# cnc_driver_5.net
KiCad netlist of a schematic drawn in EAGLE
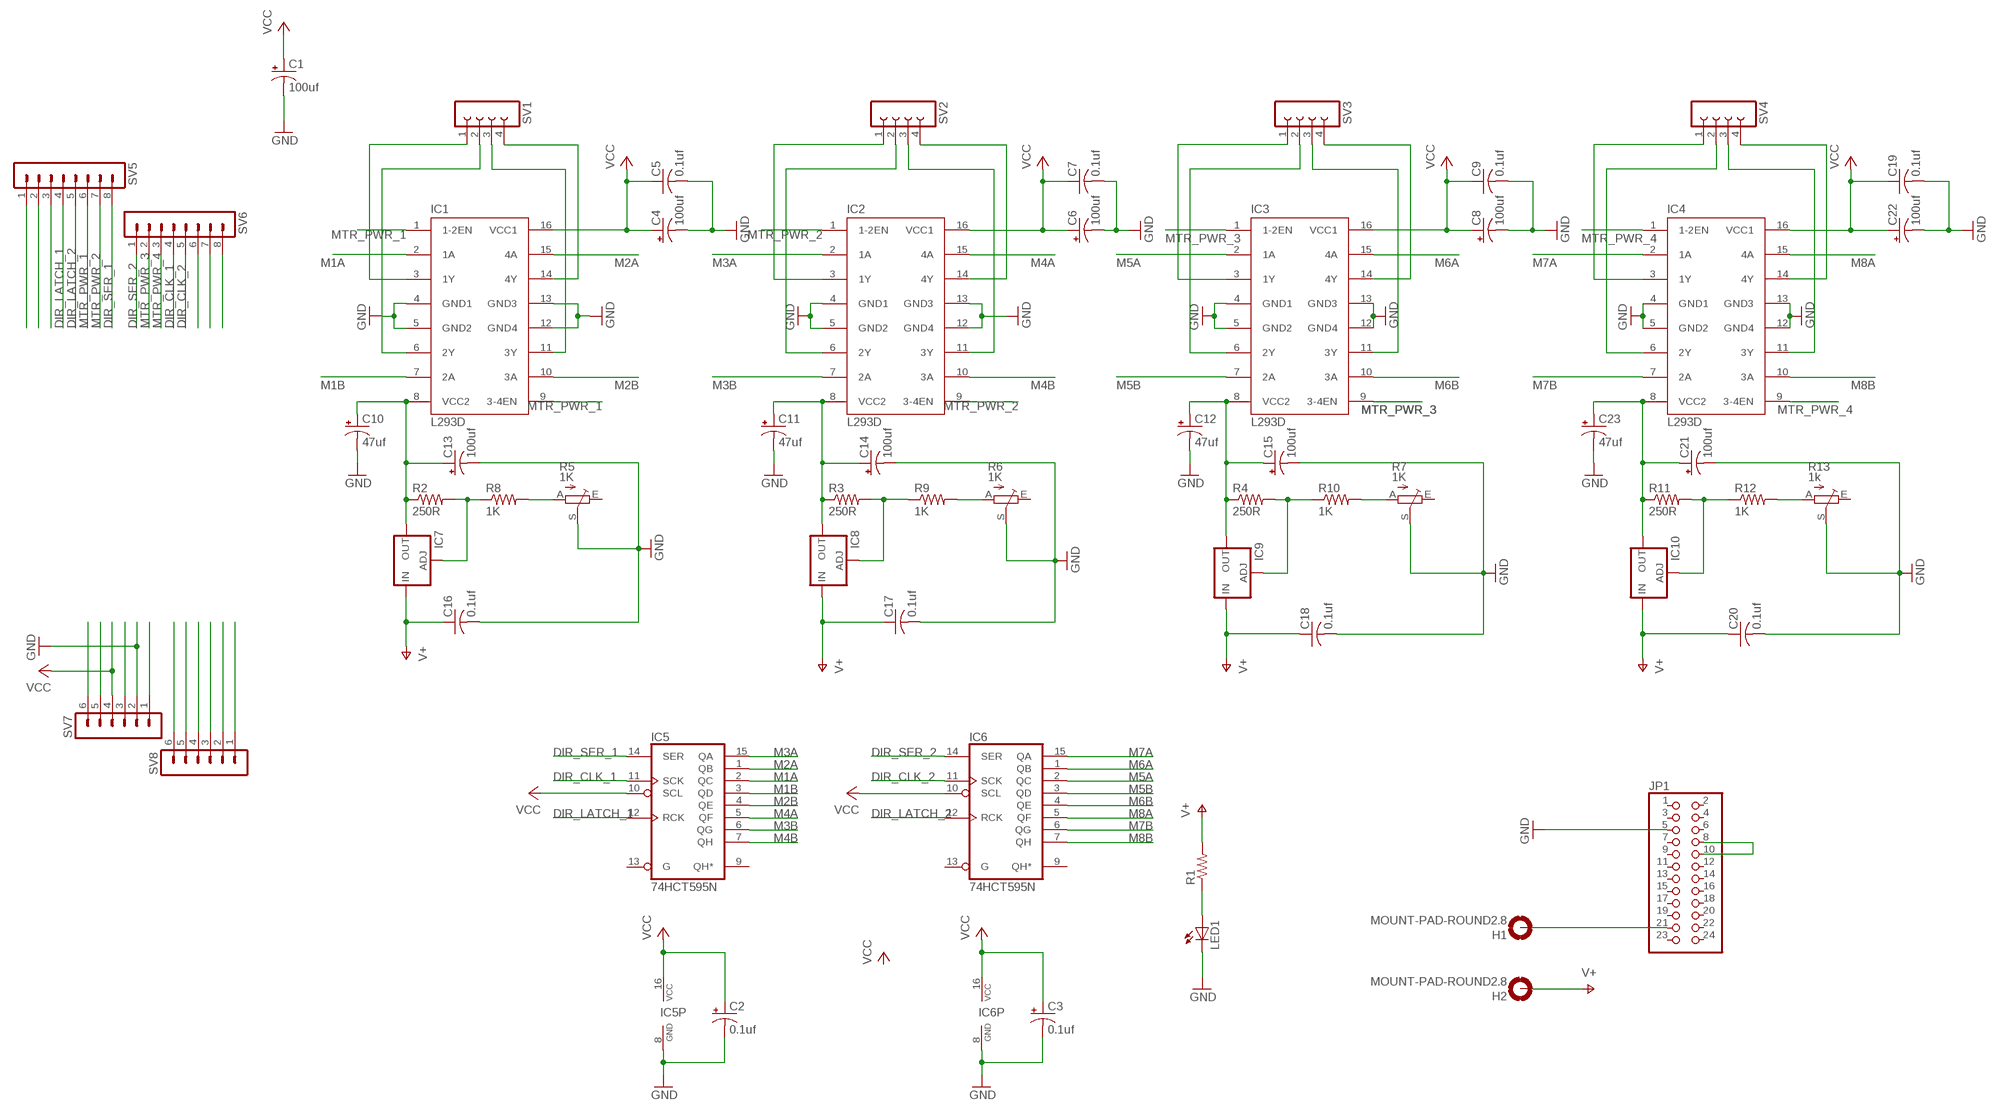
[diagram p0: schematic, sheet 1]

(export (version "E")
  (design (tool "Eeschema 10.0.6"))
  (components
    (comp (ref "C1")
      (value "100uf")
      (footprint "eagle-import:E2-5")
      (libsource (lib "eagle-import") (part "CPOL-USE2-5"))
    )
    (comp (ref "C2")
      (value "0.1uf")
      (footprint "eagle-import:E2-5")
      (libsource (lib "eagle-import") (part "CPOL-USE2-5"))
    )
    (comp (ref "C3")
      (value "0.1uf")
      (footprint "eagle-import:E2-5")
      (libsource (lib "eagle-import") (part "CPOL-USE2-5"))
    )
    (comp (ref "C4")
      (value "100uf")
      (footprint "eagle-import:E2-5")
      (libsource (lib "eagle-import") (part "CPOL-USE2-5"))
    )
    (comp (ref "C5")
      (value "0.1uf")
      (footprint "eagle-import:C025-025X050")
      (libsource (lib "eagle-import") (part "C-US025-025X050"))
    )
    (comp (ref "C6")
      (value "100uf")
      (footprint "eagle-import:E2-5")
      (libsource (lib "eagle-import") (part "CPOL-USE2-5"))
    )
    (comp (ref "C7")
      (value "0.1uf")
      (footprint "eagle-import:C025-025X050")
      (libsource (lib "eagle-import") (part "C-US025-025X050"))
    )
    (comp (ref "C8")
      (value "100uf")
      (footprint "eagle-import:E2-5")
      (libsource (lib "eagle-import") (part "CPOL-USE2-5"))
    )
    (comp (ref "C9")
      (value "0.1uf")
      (footprint "eagle-import:C025-025X050")
      (libsource (lib "eagle-import") (part "C-US025-025X050"))
    )
    (comp (ref "C10")
      (value "47uf")
      (footprint "eagle-import:E2-5")
      (libsource (lib "eagle-import") (part "CPOL-USE2-5"))
    )
    (comp (ref "C11")
      (value "47uf")
      (footprint "eagle-import:E2-5")
      (libsource (lib "eagle-import") (part "CPOL-USE2-5"))
    )
    (comp (ref "C12")
      (value "47uf")
      (footprint "eagle-import:E2-5")
      (libsource (lib "eagle-import") (part "CPOL-USE2-5"))
    )
    (comp (ref "C13")
      (value "100uf")
      (footprint "eagle-import:E3,5-8")
      (libsource (lib "eagle-import") (part "CPOL-USE3.5-8"))
    )
    (comp (ref "C14")
      (value "100uf")
      (footprint "eagle-import:E3,5-8")
      (libsource (lib "eagle-import") (part "CPOL-USE3.5-8"))
    )
    (comp (ref "C15")
      (value "100uf")
      (footprint "eagle-import:E3,5-8")
      (libsource (lib "eagle-import") (part "CPOL-USE3.5-8"))
    )
    (comp (ref "C16")
      (value "0.1uf")
      (footprint "eagle-import:C025-024X044")
      (libsource (lib "eagle-import") (part "C-US025-024X044"))
    )
    (comp (ref "C17")
      (value "0.1uf")
      (footprint "eagle-import:C025-024X044")
      (libsource (lib "eagle-import") (part "C-US025-024X044"))
    )
    (comp (ref "C18")
      (value "0.1uf")
      (footprint "eagle-import:C025-024X044")
      (libsource (lib "eagle-import") (part "C-US025-024X044"))
    )
    (comp (ref "C19")
      (value "0.1uf")
      (footprint "eagle-import:C025-025X050")
      (libsource (lib "eagle-import") (part "C-US025-025X050"))
    )
    (comp (ref "C20")
      (value "0.1uf")
      (footprint "eagle-import:C025-025X050")
      (libsource (lib "eagle-import") (part "C-US025-025X050"))
    )
    (comp (ref "C21")
      (value "100uf")
      (footprint "eagle-import:E3,5-8")
      (libsource (lib "eagle-import") (part "CPOL-USE3.5-8"))
    )
    (comp (ref "C22")
      (value "100uf")
      (footprint "eagle-import:E3,5-8")
      (libsource (lib "eagle-import") (part "CPOL-USE3.5-8"))
    )
    (comp (ref "C23")
      (value "47uf")
      (footprint "eagle-import:E3,5-8")
      (libsource (lib "eagle-import") (part "CPOL-USE3.5-8"))
    )
    (comp (ref "H1")
      (value "MOUNT-PAD-ROUND2.8")
      (footprint "eagle-import:2,8-PAD")
      (libsource (lib "eagle-import") (part "MOUNT-PAD-ROUND2.8"))
    )
    (comp (ref "H2")
      (value "MOUNT-PAD-ROUND2.8")
      (footprint "eagle-import:2,8-PAD")
      (libsource (lib "eagle-import") (part "MOUNT-PAD-ROUND2.8"))
    )
    (comp (ref "IC1")
      (value "L293D")
      (footprint "eagle-import:DIL16")
      (libsource (lib "eagle-import") (part "L293D"))
    )
    (comp (ref "IC2")
      (value "L293D")
      (footprint "eagle-import:DIL16")
      (libsource (lib "eagle-import") (part "L293D"))
    )
    (comp (ref "IC3")
      (value "L293D")
      (footprint "eagle-import:DIL16")
      (libsource (lib "eagle-import") (part "L293D"))
    )
    (comp (ref "IC4")
      (value "L293D")
      (footprint "eagle-import:DIL16")
      (libsource (lib "eagle-import") (part "L293D"))
    )
    (comp (ref "IC5")
      (value "74HCT595N")
      (footprint "eagle-import:DIL16")
      (libsource (lib "eagle-import") (part "74595NHCT"))
    )
    (comp (ref "IC6")
      (value "74HCT595N")
      (footprint "eagle-import:DIL16")
      (libsource (lib "eagle-import") (part "74595NHCT"))
    )
    (comp (ref "IC7")
      (value "LM317TS")
      (footprint "eagle-import:317TS")
      (libsource (lib "eagle-import") (part "LM317TS"))
    )
    (comp (ref "IC8")
      (value "LM317TS")
      (footprint "eagle-import:317TS")
      (libsource (lib "eagle-import") (part "LM317TS"))
    )
    (comp (ref "IC9")
      (value "LM317TS")
      (footprint "eagle-import:317TS")
      (libsource (lib "eagle-import") (part "LM317TS"))
    )
    (comp (ref "IC10")
      (value "LM317TS")
      (footprint "eagle-import:317TS")
      (libsource (lib "eagle-import") (part "LM317TS"))
    )
    (comp (ref "JP1")
      (value "PINHD-2X12")
      (footprint "eagle-import:2X12")
      (libsource (lib "eagle-import") (part "PINHD-2X12"))
    )
    (comp (ref "LED1")
      (value "LED5MM")
      (footprint "eagle-import:LED5MM")
      (libsource (lib "eagle-import") (part "LED5MM"))
    )
    (comp (ref "R1")
      (value "R-US_0204/7")
      (footprint "eagle-import:0204_7")
      (libsource (lib "eagle-import") (part "R-US_0204/7"))
    )
    (comp (ref "R2")
      (value "250R")
      (footprint "eagle-import:0207_7")
      (libsource (lib "eagle-import") (part "R-US_0207/7"))
    )
    (comp (ref "R3")
      (value "250R")
      (footprint "eagle-import:0207_7")
      (libsource (lib "eagle-import") (part "R-US_0207/7"))
    )
    (comp (ref "R4")
      (value "250R")
      (footprint "eagle-import:0207_7")
      (libsource (lib "eagle-import") (part "R-US_0207/7"))
    )
    (comp (ref "R5")
      (value "1K")
      (footprint "eagle-import:CA9H")
      (libsource (lib "eagle-import") (part "TRIM_EU-CA9H"))
    )
    (comp (ref "R6")
      (value "1K")
      (footprint "eagle-import:CA9H")
      (libsource (lib "eagle-import") (part "TRIM_EU-CA9H"))
    )
    (comp (ref "R7")
      (value "1K")
      (footprint "eagle-import:CA9H")
      (libsource (lib "eagle-import") (part "TRIM_EU-CA9H"))
    )
    (comp (ref "R8")
      (value "1K")
      (footprint "eagle-import:0207_7")
      (libsource (lib "eagle-import") (part "R-US_0207/7"))
    )
    (comp (ref "R9")
      (value "1K")
      (footprint "eagle-import:0207_7")
      (libsource (lib "eagle-import") (part "R-US_0207/7"))
    )
    (comp (ref "R10")
      (value "1K")
      (footprint "eagle-import:0207_7")
      (libsource (lib "eagle-import") (part "R-US_0207/7"))
    )
    (comp (ref "R11")
      (value "250R")
      (footprint "eagle-import:0207_7")
      (libsource (lib "eagle-import") (part "R-US_0207/7"))
    )
    (comp (ref "R12")
      (value "1K")
      (footprint "eagle-import:0207_7")
      (libsource (lib "eagle-import") (part "R-US_0207/7"))
    )
    (comp (ref "R13")
      (value "1k")
      (footprint "eagle-import:CA9H")
      (libsource (lib "eagle-import") (part "TRIM_EU-CA9H"))
    )
    (comp (ref "SV1")
      (value "FE04-1")
      (footprint "eagle-import:FE04-1")
      (libsource (lib "eagle-import") (part "FE04-1"))
    )
    (comp (ref "SV2")
      (value "FE04-1")
      (footprint "eagle-import:FE04-1")
      (libsource (lib "eagle-import") (part "FE04-1"))
    )
    (comp (ref "SV3")
      (value "FE04-1")
      (footprint "eagle-import:FE04-1")
      (libsource (lib "eagle-import") (part "FE04-1"))
    )
    (comp (ref "SV4")
      (value "FE04-1")
      (footprint "eagle-import:FE04-1")
      (libsource (lib "eagle-import") (part "FE04-1"))
    )
    (comp (ref "SV5")
      (value "MA08-1")
      (footprint "eagle-import:MA08-1")
      (libsource (lib "eagle-import") (part "MA08-1"))
    )
    (comp (ref "SV6")
      (value "MA08-1")
      (footprint "eagle-import:MA08-1")
      (libsource (lib "eagle-import") (part "MA08-1"))
    )
    (comp (ref "SV7")
      (value "MA06-1")
      (footprint "eagle-import:MA06-1")
      (libsource (lib "eagle-import") (part "MA06-1"))
    )
    (comp (ref "SV8")
      (value "MA06-1")
      (footprint "eagle-import:MA06-1")
      (libsource (lib "eagle-import") (part "MA06-1"))
    )
  )
  (nets
    (net (code "1") (name "/DIR_CLK_1") (class "Default")
      (node (ref "IC5") (pin "11") (pinfunction "SCK_11") (pintype "input"))
      (node (ref "SV6") (pin "4") (pinfunction "4_4") (pintype "passive"))
    )
    (net (code "2") (name "/DIR_CLK_2") (class "Default")
      (node (ref "IC6") (pin "11") (pinfunction "SCK_11") (pintype "input"))
      (node (ref "SV6") (pin "5") (pinfunction "5_5") (pintype "passive"))
    )
    (net (code "3") (name "/DIR_LATCH_1") (class "Default")
      (node (ref "IC5") (pin "12") (pinfunction "RCK_12") (pintype "input"))
      (node (ref "SV5") (pin "4") (pinfunction "4_4") (pintype "passive"))
    )
    (net (code "4") (name "/DIR_LATCH_2") (class "Default")
      (node (ref "IC6") (pin "12") (pinfunction "RCK_12") (pintype "input"))
      (node (ref "SV5") (pin "5") (pinfunction "5_5") (pintype "passive"))
    )
    (net (code "5") (name "/DIR_SER_1") (class "Default")
      (node (ref "IC5") (pin "14") (pinfunction "SER_14") (pintype "input"))
      (node (ref "SV5") (pin "8") (pinfunction "8_8") (pintype "passive"))
    )
    (net (code "6") (name "/DIR_SER_2") (class "Default")
      (node (ref "IC6") (pin "14") (pinfunction "SER_14") (pintype "input"))
      (node (ref "SV6") (pin "1") (pinfunction "1_1") (pintype "passive"))
    )
    (net (code "7") (name "/M1A") (class "Default")
      (node (ref "IC1") (pin "2") (pinfunction "1A_2") (pintype "input"))
      (node (ref "IC5") (pin "2") (pinfunction "QC_2") (pintype "tri_state"))
    )
    (net (code "8") (name "/M1B") (class "Default")
      (node (ref "IC1") (pin "7") (pinfunction "2A_7") (pintype "input"))
      (node (ref "IC5") (pin "3") (pinfunction "QD_3") (pintype "tri_state"))
    )
    (net (code "9") (name "/M2A") (class "Default")
      (node (ref "IC1") (pin "15") (pinfunction "4A_15") (pintype "input"))
      (node (ref "IC5") (pin "1") (pinfunction "QB_1") (pintype "tri_state"))
    )
    (net (code "10") (name "/M2B") (class "Default")
      (node (ref "IC1") (pin "10") (pinfunction "3A_10") (pintype "input"))
      (node (ref "IC5") (pin "4") (pinfunction "QE_4") (pintype "tri_state"))
    )
    (net (code "11") (name "/M3A") (class "Default")
      (node (ref "IC2") (pin "2") (pinfunction "1A_2") (pintype "input"))
      (node (ref "IC5") (pin "15") (pinfunction "QA_15") (pintype "tri_state"))
    )
    (net (code "12") (name "/M3B") (class "Default")
      (node (ref "IC2") (pin "7") (pinfunction "2A_7") (pintype "input"))
      (node (ref "IC5") (pin "6") (pinfunction "QG_6") (pintype "tri_state"))
    )
    (net (code "13") (name "/M4A") (class "Default")
      (node (ref "IC2") (pin "15") (pinfunction "4A_15") (pintype "input"))
      (node (ref "IC5") (pin "5") (pinfunction "QF_5") (pintype "tri_state"))
    )
    (net (code "14") (name "/M4B") (class "Default")
      (node (ref "IC2") (pin "10") (pinfunction "3A_10") (pintype "input"))
      (node (ref "IC5") (pin "7") (pinfunction "QH_7") (pintype "tri_state"))
    )
    (net (code "15") (name "/M5A") (class "Default")
      (node (ref "IC3") (pin "2") (pinfunction "1A_2") (pintype "input"))
      (node (ref "IC6") (pin "2") (pinfunction "QC_2") (pintype "tri_state"))
    )
    (net (code "16") (name "/M5B") (class "Default")
      (node (ref "IC3") (pin "7") (pinfunction "2A_7") (pintype "input"))
      (node (ref "IC6") (pin "3") (pinfunction "QD_3") (pintype "tri_state"))
    )
    (net (code "17") (name "/M6A") (class "Default")
      (node (ref "IC3") (pin "15") (pinfunction "4A_15") (pintype "input"))
      (node (ref "IC6") (pin "1") (pinfunction "QB_1") (pintype "tri_state"))
    )
    (net (code "18") (name "/M6B") (class "Default")
      (node (ref "IC3") (pin "10") (pinfunction "3A_10") (pintype "input"))
      (node (ref "IC6") (pin "4") (pinfunction "QE_4") (pintype "tri_state"))
    )
    (net (code "19") (name "/M7A") (class "Default")
      (node (ref "IC4") (pin "2") (pinfunction "1A_2") (pintype "input"))
      (node (ref "IC6") (pin "15") (pinfunction "QA_15") (pintype "tri_state"))
    )
    (net (code "20") (name "/M7B") (class "Default")
      (node (ref "IC4") (pin "7") (pinfunction "2A_7") (pintype "input"))
      (node (ref "IC6") (pin "6") (pinfunction "QG_6") (pintype "tri_state"))
    )
    (net (code "21") (name "/M8A") (class "Default")
      (node (ref "IC4") (pin "15") (pinfunction "4A_15") (pintype "input"))
      (node (ref "IC6") (pin "5") (pinfunction "QF_5") (pintype "tri_state"))
    )
    (net (code "22") (name "/M8B") (class "Default")
      (node (ref "IC4") (pin "10") (pinfunction "3A_10") (pintype "input"))
      (node (ref "IC6") (pin "7") (pinfunction "QH_7") (pintype "tri_state"))
    )
    (net (code "23") (name "/MTR_PWR_1") (class "Default")
      (node (ref "IC1") (pin "1") (pinfunction "1-2EN_1") (pintype "input"))
      (node (ref "IC1") (pin "9") (pinfunction "3-4EN_9") (pintype "input"))
      (node (ref "SV5") (pin "6") (pinfunction "6_6") (pintype "passive"))
    )
    (net (code "24") (name "/MTR_PWR_2") (class "Default")
      (node (ref "IC2") (pin "1") (pinfunction "1-2EN_1") (pintype "input"))
      (node (ref "IC2") (pin "9") (pinfunction "3-4EN_9") (pintype "input"))
      (node (ref "SV5") (pin "7") (pinfunction "7_7") (pintype "passive"))
    )
    (net (code "25") (name "/MTR_PWR_3") (class "Default")
      (node (ref "IC3") (pin "1") (pinfunction "1-2EN_1") (pintype "input"))
      (node (ref "IC3") (pin "9") (pinfunction "3-4EN_9") (pintype "input"))
      (node (ref "SV6") (pin "2") (pinfunction "2_2") (pintype "passive"))
    )
    (net (code "26") (name "/MTR_PWR_4") (class "Default")
      (node (ref "IC4") (pin "1") (pinfunction "1-2EN_1") (pintype "input"))
      (node (ref "IC4") (pin "9") (pinfunction "3-4EN_9") (pintype "input"))
      (node (ref "SV6") (pin "3") (pinfunction "3_3") (pintype "passive"))
    )
    (net (code "27") (name "GND") (class "Default")
      (node (ref "C1") (pin "-") (pinfunction "-_-") (pintype "passive"))
      (node (ref "C10") (pin "-") (pinfunction "-_-") (pintype "passive"))
      (node (ref "C11") (pin "-") (pinfunction "-_-") (pintype "passive"))
      (node (ref "C12") (pin "-") (pinfunction "-_-") (pintype "passive"))
      (node (ref "C13") (pin "-") (pinfunction "-_-") (pintype "passive"))
      (node (ref "C14") (pin "-") (pinfunction "-_-") (pintype "passive"))
      (node (ref "C15") (pin "-") (pinfunction "-_-") (pintype "passive"))
      (node (ref "C16") (pin "2") (pinfunction "2_2") (pintype "passive"))
      (node (ref "C17") (pin "2") (pinfunction "2_2") (pintype "passive"))
      (node (ref "C18") (pin "2") (pinfunction "2_2") (pintype "passive"))
      (node (ref "C19") (pin "2") (pinfunction "2_2") (pintype "passive"))
      (node (ref "C2") (pin "-") (pinfunction "-_-") (pintype "passive"))
      (node (ref "C20") (pin "2") (pinfunction "2_2") (pintype "passive"))
      (node (ref "C21") (pin "-") (pinfunction "-_-") (pintype "passive"))
      (node (ref "C22") (pin "-") (pinfunction "-_-") (pintype "passive"))
      (node (ref "C23") (pin "-") (pinfunction "-_-") (pintype "passive"))
      (node (ref "C3") (pin "-") (pinfunction "-_-") (pintype "passive"))
      (node (ref "C4") (pin "-") (pinfunction "-_-") (pintype "passive"))
      (node (ref "C5") (pin "2") (pinfunction "2_2") (pintype "passive"))
      (node (ref "C6") (pin "-") (pinfunction "-_-") (pintype "passive"))
      (node (ref "C7") (pin "2") (pinfunction "2_2") (pintype "passive"))
      (node (ref "C8") (pin "-") (pinfunction "-_-") (pintype "passive"))
      (node (ref "C9") (pin "2") (pinfunction "2_2") (pintype "passive"))
      (node (ref "IC1") (pin "12") (pinfunction "GND4_12") (pintype "power_in"))
      (node (ref "IC1") (pin "13") (pinfunction "GND3_13") (pintype "power_in"))
      (node (ref "IC1") (pin "4") (pinfunction "GND1_4") (pintype "power_in"))
      (node (ref "IC1") (pin "5") (pinfunction "GND2_5") (pintype "power_in"))
      (node (ref "IC2") (pin "12") (pinfunction "GND4_12") (pintype "power_in"))
      (node (ref "IC2") (pin "13") (pinfunction "GND3_13") (pintype "power_in"))
      (node (ref "IC2") (pin "4") (pinfunction "GND1_4") (pintype "power_in"))
      (node (ref "IC2") (pin "5") (pinfunction "GND2_5") (pintype "power_in"))
      (node (ref "IC3") (pin "12") (pinfunction "GND4_12") (pintype "power_in"))
      (node (ref "IC3") (pin "13") (pinfunction "GND3_13") (pintype "power_in"))
      (node (ref "IC3") (pin "4") (pinfunction "GND1_4") (pintype "power_in"))
      (node (ref "IC3") (pin "5") (pinfunction "GND2_5") (pintype "power_in"))
      (node (ref "IC4") (pin "12") (pinfunction "GND4_12") (pintype "power_in"))
      (node (ref "IC4") (pin "13") (pinfunction "GND3_13") (pintype "power_in"))
      (node (ref "IC4") (pin "4") (pinfunction "GND1_4") (pintype "power_in"))
      (node (ref "IC4") (pin "5") (pinfunction "GND2_5") (pintype "power_in"))
      (node (ref "IC5") (pin "8") (pinfunction "GND_8") (pintype "power_in"))
      (node (ref "IC6") (pin "8") (pinfunction "GND_8") (pintype "power_in"))
      (node (ref "JP1") (pin "5") (pinfunction "5_5") (pintype "passive"))
      (node (ref "LED1") (pin "K") (pinfunction "C_K") (pintype "passive"))
      (node (ref "R13") (pin "S") (pinfunction "S_S") (pintype "passive"))
      (node (ref "R5") (pin "S") (pinfunction "S_S") (pintype "passive"))
      (node (ref "R6") (pin "S") (pinfunction "S_S") (pintype "passive"))
      (node (ref "R7") (pin "S") (pinfunction "S_S") (pintype "passive"))
      (node (ref "SV7") (pin "2") (pinfunction "2_2") (pintype "passive"))
    )
    (net (code "28") (name "Net-(H1-MOUNT)") (class "Default")
      (node (ref "H1") (pin "B2,8") (pinfunction "MOUNT_B2,8") (pintype "passive"))
      (node (ref "JP1") (pin "21") (pinfunction "21_21") (pintype "passive"))
    )
    (net (code "29") (name "Net-(IC1-1Y)") (class "Default")
      (node (ref "IC1") (pin "3") (pinfunction "1Y_3") (pintype "output"))
      (node (ref "SV1") (pin "1") (pinfunction "1_1") (pintype "passive"))
    )
    (net (code "30") (name "Net-(IC1-2Y)") (class "Default")
      (node (ref "IC1") (pin "6") (pinfunction "2Y_6") (pintype "output"))
      (node (ref "SV1") (pin "2") (pinfunction "2_2") (pintype "passive"))
    )
    (net (code "31") (name "Net-(IC1-3Y)") (class "Default")
      (node (ref "IC1") (pin "11") (pinfunction "3Y_11") (pintype "output"))
      (node (ref "SV1") (pin "3") (pinfunction "3_3") (pintype "passive"))
    )
    (net (code "32") (name "Net-(IC1-4Y)") (class "Default")
      (node (ref "IC1") (pin "14") (pinfunction "4Y_14") (pintype "output"))
      (node (ref "SV1") (pin "4") (pinfunction "4_4") (pintype "passive"))
    )
    (net (code "33") (name "Net-(IC1-VCC2)") (class "Default")
      (node (ref "C10") (pin "+") (pinfunction "+_+") (pintype "passive"))
      (node (ref "C13") (pin "+") (pinfunction "+_+") (pintype "passive"))
      (node (ref "IC1") (pin "8") (pinfunction "VCC2_8") (pintype "power_in"))
      (node (ref "IC7") (pin "2") (pinfunction "OUT_2") (pintype "passive"))
      (node (ref "R2") (pin "1") (pinfunction "1_1") (pintype "passive"))
    )
    (net (code "34") (name "Net-(IC2-1Y)") (class "Default")
      (node (ref "IC2") (pin "3") (pinfunction "1Y_3") (pintype "output"))
      (node (ref "SV2") (pin "1") (pinfunction "1_1") (pintype "passive"))
    )
    (net (code "35") (name "Net-(IC2-2Y)") (class "Default")
      (node (ref "IC2") (pin "6") (pinfunction "2Y_6") (pintype "output"))
      (node (ref "SV2") (pin "2") (pinfunction "2_2") (pintype "passive"))
    )
    (net (code "36") (name "Net-(IC2-3Y)") (class "Default")
      (node (ref "IC2") (pin "11") (pinfunction "3Y_11") (pintype "output"))
      (node (ref "SV2") (pin "3") (pinfunction "3_3") (pintype "passive"))
    )
    (net (code "37") (name "Net-(IC2-4Y)") (class "Default")
      (node (ref "IC2") (pin "14") (pinfunction "4Y_14") (pintype "output"))
      (node (ref "SV2") (pin "4") (pinfunction "4_4") (pintype "passive"))
    )
    (net (code "38") (name "Net-(IC2-VCC2)") (class "Default")
      (node (ref "C11") (pin "+") (pinfunction "+_+") (pintype "passive"))
      (node (ref "C14") (pin "+") (pinfunction "+_+") (pintype "passive"))
      (node (ref "IC2") (pin "8") (pinfunction "VCC2_8") (pintype "power_in"))
      (node (ref "IC8") (pin "2") (pinfunction "OUT_2") (pintype "passive"))
      (node (ref "R3") (pin "1") (pinfunction "1_1") (pintype "passive"))
    )
    (net (code "39") (name "Net-(IC3-1Y)") (class "Default")
      (node (ref "IC3") (pin "3") (pinfunction "1Y_3") (pintype "output"))
      (node (ref "SV3") (pin "1") (pinfunction "1_1") (pintype "passive"))
    )
    (net (code "40") (name "Net-(IC3-2Y)") (class "Default")
      (node (ref "IC3") (pin "6") (pinfunction "2Y_6") (pintype "output"))
      (node (ref "SV3") (pin "2") (pinfunction "2_2") (pintype "passive"))
    )
    (net (code "41") (name "Net-(IC3-3Y)") (class "Default")
      (node (ref "IC3") (pin "11") (pinfunction "3Y_11") (pintype "output"))
      (node (ref "SV3") (pin "3") (pinfunction "3_3") (pintype "passive"))
    )
    (net (code "42") (name "Net-(IC3-4Y)") (class "Default")
      (node (ref "IC3") (pin "14") (pinfunction "4Y_14") (pintype "output"))
      (node (ref "SV3") (pin "4") (pinfunction "4_4") (pintype "passive"))
    )
    (net (code "43") (name "Net-(IC3-VCC2)") (class "Default")
      (node (ref "C12") (pin "+") (pinfunction "+_+") (pintype "passive"))
      (node (ref "C15") (pin "+") (pinfunction "+_+") (pintype "passive"))
      (node (ref "IC3") (pin "8") (pinfunction "VCC2_8") (pintype "power_in"))
      (node (ref "IC9") (pin "2") (pinfunction "OUT_2") (pintype "passive"))
      (node (ref "R4") (pin "1") (pinfunction "1_1") (pintype "passive"))
    )
    (net (code "44") (name "Net-(IC4-1Y)") (class "Default")
      (node (ref "IC4") (pin "3") (pinfunction "1Y_3") (pintype "output"))
      (node (ref "SV4") (pin "1") (pinfunction "1_1") (pintype "passive"))
    )
    (net (code "45") (name "Net-(IC4-2Y)") (class "Default")
      (node (ref "IC4") (pin "6") (pinfunction "2Y_6") (pintype "output"))
      (node (ref "SV4") (pin "2") (pinfunction "2_2") (pintype "passive"))
    )
    (net (code "46") (name "Net-(IC4-3Y)") (class "Default")
      (node (ref "IC4") (pin "11") (pinfunction "3Y_11") (pintype "output"))
      (node (ref "SV4") (pin "3") (pinfunction "3_3") (pintype "passive"))
    )
    (net (code "47") (name "Net-(IC4-4Y)") (class "Default")
      (node (ref "IC4") (pin "14") (pinfunction "4Y_14") (pintype "output"))
      (node (ref "SV4") (pin "4") (pinfunction "4_4") (pintype "passive"))
    )
    (net (code "48") (name "Net-(IC7-ADJ)") (class "Default")
      (node (ref "IC7") (pin "1") (pinfunction "ADJ_1") (pintype "input"))
      (node (ref "R2") (pin "2") (pinfunction "2_2") (pintype "passive"))
      (node (ref "R8") (pin "1") (pinfunction "1_1") (pintype "passive"))
    )
    (net (code "49") (name "Net-(IC8-ADJ)") (class "Default")
      (node (ref "IC8") (pin "1") (pinfunction "ADJ_1") (pintype "input"))
      (node (ref "R3") (pin "2") (pinfunction "2_2") (pintype "passive"))
      (node (ref "R9") (pin "1") (pinfunction "1_1") (pintype "passive"))
    )
    (net (code "50") (name "Net-(IC9-ADJ)") (class "Default")
      (node (ref "IC9") (pin "1") (pinfunction "ADJ_1") (pintype "input"))
      (node (ref "R10") (pin "1") (pinfunction "1_1") (pintype "passive"))
      (node (ref "R4") (pin "2") (pinfunction "2_2") (pintype "passive"))
    )
    (net (code "51") (name "Net-(IC10-ADJ)") (class "Default")
      (node (ref "IC10") (pin "1") (pinfunction "ADJ_1") (pintype "input"))
      (node (ref "R11") (pin "2") (pinfunction "2_2") (pintype "passive"))
      (node (ref "R12") (pin "1") (pinfunction "1_1") (pintype "passive"))
    )
    (net (code "52") (name "Net-(IC10-OUT)") (class "Default")
      (node (ref "C21") (pin "+") (pinfunction "+_+") (pintype "passive"))
      (node (ref "C23") (pin "+") (pinfunction "+_+") (pintype "passive"))
      (node (ref "IC10") (pin "2") (pinfunction "OUT_2") (pintype "passive"))
      (node (ref "IC4") (pin "8") (pinfunction "VCC2_8") (pintype "power_in"))
      (node (ref "R11") (pin "1") (pinfunction "1_1") (pintype "passive"))
    )
    (net (code "53") (name "Net-(JP1-Pad10)") (class "Default")
      (node (ref "JP1") (pin "10") (pinfunction "10_10") (pintype "passive"))
      (node (ref "JP1") (pin "8") (pinfunction "8_8") (pintype "passive"))
    )
    (net (code "54") (name "Net-(LED1-PadA)") (class "Default")
      (node (ref "LED1") (pin "A") (pinfunction "A_A") (pintype "passive"))
      (node (ref "R1") (pin "1") (pinfunction "1_1") (pintype "passive"))
    )
    (net (code "55") (name "Net-(R5-PadA)") (class "Default")
      (node (ref "R5") (pin "A") (pinfunction "A_A") (pintype "passive"))
      (node (ref "R8") (pin "2") (pinfunction "2_2") (pintype "passive"))
    )
    (net (code "56") (name "Net-(R6-PadA)") (class "Default")
      (node (ref "R6") (pin "A") (pinfunction "A_A") (pintype "passive"))
      (node (ref "R9") (pin "2") (pinfunction "2_2") (pintype "passive"))
    )
    (net (code "57") (name "Net-(R10-Pad2)") (class "Default")
      (node (ref "R10") (pin "2") (pinfunction "2_2") (pintype "passive"))
      (node (ref "R7") (pin "A") (pinfunction "A_A") (pintype "passive"))
    )
    (net (code "58") (name "Net-(R12-Pad2)") (class "Default")
      (node (ref "R12") (pin "2") (pinfunction "2_2") (pintype "passive"))
      (node (ref "R13") (pin "A") (pinfunction "A_A") (pintype "passive"))
    )
    (net (code "59") (name "V+") (class "Default")
      (node (ref "C16") (pin "1") (pinfunction "1_1") (pintype "passive"))
      (node (ref "C17") (pin "1") (pinfunction "1_1") (pintype "passive"))
      (node (ref "C18") (pin "1") (pinfunction "1_1") (pintype "passive"))
      (node (ref "C20") (pin "1") (pinfunction "1_1") (pintype "passive"))
      (node (ref "H2") (pin "B2,8") (pinfunction "MOUNT_B2,8") (pintype "passive"))
      (node (ref "IC10") (pin "3") (pinfunction "IN_3") (pintype "input"))
      (node (ref "IC7") (pin "3") (pinfunction "IN_3") (pintype "input"))
      (node (ref "IC8") (pin "3") (pinfunction "IN_3") (pintype "input"))
      (node (ref "IC9") (pin "3") (pinfunction "IN_3") (pintype "input"))
      (node (ref "R1") (pin "2") (pinfunction "2_2") (pintype "passive"))
    )
    (net (code "60") (name "VCC") (class "Default")
      (node (ref "C1") (pin "+") (pinfunction "+_+") (pintype "passive"))
      (node (ref "C19") (pin "1") (pinfunction "1_1") (pintype "passive"))
      (node (ref "C2") (pin "+") (pinfunction "+_+") (pintype "passive"))
      (node (ref "C22") (pin "+") (pinfunction "+_+") (pintype "passive"))
      (node (ref "C3") (pin "+") (pinfunction "+_+") (pintype "passive"))
      (node (ref "C4") (pin "+") (pinfunction "+_+") (pintype "passive"))
      (node (ref "C5") (pin "1") (pinfunction "1_1") (pintype "passive"))
      (node (ref "C6") (pin "+") (pinfunction "+_+") (pintype "passive"))
      (node (ref "C7") (pin "1") (pinfunction "1_1") (pintype "passive"))
      (node (ref "C8") (pin "+") (pinfunction "+_+") (pintype "passive"))
      (node (ref "C9") (pin "1") (pinfunction "1_1") (pintype "passive"))
      (node (ref "IC1") (pin "16") (pinfunction "VCC1_16") (pintype "power_in"))
      (node (ref "IC2") (pin "16") (pinfunction "VCC1_16") (pintype "power_in"))
      (node (ref "IC3") (pin "16") (pinfunction "VCC1_16") (pintype "power_in"))
      (node (ref "IC4") (pin "16") (pinfunction "VCC1_16") (pintype "power_in"))
      (node (ref "IC5") (pin "10") (pinfunction "SCL_10") (pintype "input"))
      (node (ref "IC5") (pin "16") (pinfunction "VCC_16") (pintype "power_in"))
      (node (ref "IC6") (pin "10") (pinfunction "SCL_10") (pintype "input"))
      (node (ref "IC6") (pin "16") (pinfunction "VCC_16") (pintype "power_in"))
      (node (ref "SV7") (pin "4") (pinfunction "4_4") (pintype "passive"))
    )
    (net (code "61") (name "unconnected-(IC5A-G-Pad13)") (class "Default")
      (node (ref "IC5") (pin "13") (pinfunction "G_13") (pintype "input"))
    )
    (net (code "62") (name "unconnected-(IC5A-QH*-Pad9)") (class "Default")
      (node (ref "IC5") (pin "9") (pinfunction "QH*_9") (pintype "tri_state"))
    )
    (net (code "63") (name "unconnected-(IC6A-G-Pad13)") (class "Default")
      (node (ref "IC6") (pin "13") (pinfunction "G_13") (pintype "input"))
    )
    (net (code "64") (name "unconnected-(IC6A-QH*-Pad9)") (class "Default")
      (node (ref "IC6") (pin "9") (pinfunction "QH*_9") (pintype "tri_state"))
    )
    (net (code "65") (name "unconnected-(JP1-Pad1)") (class "Default")
      (node (ref "JP1") (pin "1") (pinfunction "1_1") (pintype "passive"))
    )
    (net (code "66") (name "unconnected-(JP1-Pad2)") (class "Default")
      (node (ref "JP1") (pin "2") (pinfunction "2_2") (pintype "passive"))
    )
    (net (code "67") (name "unconnected-(JP1-Pad3)") (class "Default")
      (node (ref "JP1") (pin "3") (pinfunction "3_3") (pintype "passive"))
    )
    (net (code "68") (name "unconnected-(JP1-Pad4)") (class "Default")
      (node (ref "JP1") (pin "4") (pinfunction "4_4") (pintype "passive"))
    )
    (net (code "69") (name "unconnected-(JP1-Pad6)") (class "Default")
      (node (ref "JP1") (pin "6") (pinfunction "6_6") (pintype "passive"))
    )
    (net (code "70") (name "unconnected-(JP1-Pad7)") (class "Default")
      (node (ref "JP1") (pin "7") (pinfunction "7_7") (pintype "passive"))
    )
    (net (code "71") (name "unconnected-(JP1-Pad9)") (class "Default")
      (node (ref "JP1") (pin "9") (pinfunction "9_9") (pintype "passive"))
    )
    (net (code "72") (name "unconnected-(JP1-Pad11)") (class "Default")
      (node (ref "JP1") (pin "11") (pinfunction "11_11") (pintype "passive"))
    )
    (net (code "73") (name "unconnected-(JP1-Pad12)") (class "Default")
      (node (ref "JP1") (pin "12") (pinfunction "12_12") (pintype "passive"))
    )
    (net (code "74") (name "unconnected-(JP1-Pad13)") (class "Default")
      (node (ref "JP1") (pin "13") (pinfunction "13_13") (pintype "passive"))
    )
    (net (code "75") (name "unconnected-(JP1-Pad14)") (class "Default")
      (node (ref "JP1") (pin "14") (pinfunction "14_14") (pintype "passive"))
    )
    (net (code "76") (name "unconnected-(JP1-Pad15)") (class "Default")
      (node (ref "JP1") (pin "15") (pinfunction "15_15") (pintype "passive"))
    )
    (net (code "77") (name "unconnected-(JP1-Pad16)") (class "Default")
      (node (ref "JP1") (pin "16") (pinfunction "16_16") (pintype "passive"))
    )
    (net (code "78") (name "unconnected-(JP1-Pad17)") (class "Default")
      (node (ref "JP1") (pin "17") (pinfunction "17_17") (pintype "passive"))
    )
    (net (code "79") (name "unconnected-(JP1-Pad18)") (class "Default")
      (node (ref "JP1") (pin "18") (pinfunction "18_18") (pintype "passive"))
    )
    (net (code "80") (name "unconnected-(JP1-Pad19)") (class "Default")
      (node (ref "JP1") (pin "19") (pinfunction "19_19") (pintype "passive"))
    )
    (net (code "81") (name "unconnected-(JP1-Pad20)") (class "Default")
      (node (ref "JP1") (pin "20") (pinfunction "20_20") (pintype "passive"))
    )
    (net (code "82") (name "unconnected-(JP1-Pad22)") (class "Default")
      (node (ref "JP1") (pin "22") (pinfunction "22_22") (pintype "passive"))
    )
    (net (code "83") (name "unconnected-(JP1-Pad23)") (class "Default")
      (node (ref "JP1") (pin "23") (pinfunction "23_23") (pintype "passive"))
    )
    (net (code "84") (name "unconnected-(JP1-Pad24)") (class "Default")
      (node (ref "JP1") (pin "24") (pinfunction "24_24") (pintype "passive"))
    )
    (net (code "85") (name "unconnected-(R5-PadE)") (class "Default")
      (node (ref "R5") (pin "E") (pinfunction "E_E") (pintype "passive"))
    )
    (net (code "86") (name "unconnected-(R6-PadE)") (class "Default")
      (node (ref "R6") (pin "E") (pinfunction "E_E") (pintype "passive"))
    )
    (net (code "87") (name "unconnected-(R7-PadE)") (class "Default")
      (node (ref "R7") (pin "E") (pinfunction "E_E") (pintype "passive"))
    )
    (net (code "88") (name "unconnected-(R13-PadE)") (class "Default")
      (node (ref "R13") (pin "E") (pinfunction "E_E") (pintype "passive"))
    )
    (net (code "89") (name "unconnected-(SV5-Pad1)") (class "Default")
      (node (ref "SV5") (pin "1") (pinfunction "1_1") (pintype "passive"))
    )
    (net (code "90") (name "unconnected-(SV5-Pad2)") (class "Default")
      (node (ref "SV5") (pin "2") (pinfunction "2_2") (pintype "passive"))
    )
    (net (code "91") (name "unconnected-(SV5-Pad3)") (class "Default")
      (node (ref "SV5") (pin "3") (pinfunction "3_3") (pintype "passive"))
    )
    (net (code "92") (name "unconnected-(SV6-Pad6)") (class "Default")
      (node (ref "SV6") (pin "6") (pinfunction "6_6") (pintype "passive"))
    )
    (net (code "93") (name "unconnected-(SV6-Pad7)") (class "Default")
      (node (ref "SV6") (pin "7") (pinfunction "7_7") (pintype "passive"))
    )
    (net (code "94") (name "unconnected-(SV6-Pad8)") (class "Default")
      (node (ref "SV6") (pin "8") (pinfunction "8_8") (pintype "passive"))
    )
    (net (code "95") (name "unconnected-(SV7-Pad1)") (class "Default")
      (node (ref "SV7") (pin "1") (pinfunction "1_1") (pintype "passive"))
    )
    (net (code "96") (name "unconnected-(SV7-Pad3)") (class "Default")
      (node (ref "SV7") (pin "3") (pinfunction "3_3") (pintype "passive"))
    )
    (net (code "97") (name "unconnected-(SV7-Pad5)") (class "Default")
      (node (ref "SV7") (pin "5") (pinfunction "5_5") (pintype "passive"))
    )
    (net (code "98") (name "unconnected-(SV7-Pad6)") (class "Default")
      (node (ref "SV7") (pin "6") (pinfunction "6_6") (pintype "passive"))
    )
    (net (code "99") (name "unconnected-(SV8-Pad1)") (class "Default")
      (node (ref "SV8") (pin "1") (pinfunction "1_1") (pintype "passive"))
    )
    (net (code "100") (name "unconnected-(SV8-Pad2)") (class "Default")
      (node (ref "SV8") (pin "2") (pinfunction "2_2") (pintype "passive"))
    )
    (net (code "101") (name "unconnected-(SV8-Pad3)") (class "Default")
      (node (ref "SV8") (pin "3") (pinfunction "3_3") (pintype "passive"))
    )
    (net (code "102") (name "unconnected-(SV8-Pad4)") (class "Default")
      (node (ref "SV8") (pin "4") (pinfunction "4_4") (pintype "passive"))
    )
    (net (code "103") (name "unconnected-(SV8-Pad5)") (class "Default")
      (node (ref "SV8") (pin "5") (pinfunction "5_5") (pintype "passive"))
    )
    (net (code "104") (name "unconnected-(SV8-Pad6)") (class "Default")
      (node (ref "SV8") (pin "6") (pinfunction "6_6") (pintype "passive"))
    )
  )
)
